# 01_Zasilacz.net
KiCad netlist of a schematic drawn in Altium Designer
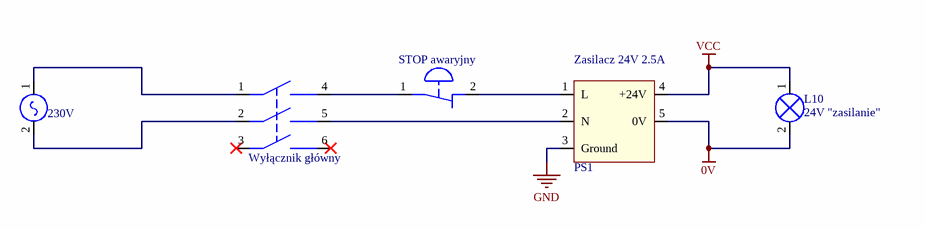
[diagram p0: [01] Zasilacz.SchDoc]

(export (version "E")
  (design (tool "Eeschema 10.0.6"))
  (components
    (comp (ref "*") (value "230V") (libsource (lib "Schlib2") (part "230V source")))
    (comp (ref "L10") (value "24V \"zasilanie\"") (libsource (lib "Schlib2") (part "Light")))
    (comp (ref "PS1") (value "Zasilacz 24V 2.5A") (libsource (lib "Schlib2") (part "Power supply")))
    (comp (ref "STOP awaryjny") (value "E-STOP 1 line") (libsource (lib "Schlib2") (part "E-STOP 1 line")))
    (comp (ref "Wyłącznik główny")
      (value "Power switch")
      (libsource (lib "Szczotkarka") (part "Power switch"))
    )
  )
  (nets
    (net (code "1") (name "0V") (class "Default")
      (node (ref "L10") (pin "2") (pinfunction "*_2") (pintype "passive"))
      (node (ref "PS1") (pin "5") (pinfunction "0V_5") (pintype "passive"))
    )
    (net (code "2") (name "GND") (class "Default")
      (node (ref "PS1") (pin "3") (pinfunction "Ground_3") (pintype "passive"))
    )
    (net (code "3") (name "Net-(PS1-L)") (class "Default")
      (node (ref "PS1") (pin "1") (pinfunction "L_1") (pintype "passive"))
      (node (ref "STOP awaryjny") (pin "2") (pinfunction "*_2") (pintype "passive"))
    )
    (net (code "4") (name "Net-(PS1-N)") (class "Default")
      (node (ref "PS1") (pin "2") (pinfunction "N_2") (pintype "passive"))
      (node (ref "Wyłącznik główny") (pin "5") (pinfunction "18_5") (pintype "passive"))
    )
    (net (code "5") (name "Net-(Wyłącznik główny-14)") (class "Default")
      (node (ref "*") (pin "1") (pinfunction "*_1") (pintype "passive"))
      (node (ref "Wyłącznik główny") (pin "1") (pinfunction "14_1") (pintype "passive"))
    )
    (net (code "6") (name "Net-(Wyłącznik główny-15)") (class "Default")
      (node (ref "*") (pin "2") (pinfunction "*_2") (pintype "passive"))
      (node (ref "Wyłącznik główny") (pin "2") (pinfunction "15_2") (pintype "passive"))
    )
    (net (code "7") (name "Net-(Wyłącznik główny-17)") (class "Default")
      (node (ref "STOP awaryjny") (pin "1") (pinfunction "*_1") (pintype "passive"))
      (node (ref "Wyłącznik główny") (pin "4") (pinfunction "17_4") (pintype "passive"))
    )
    (net (code "8") (name "VCC") (class "Default")
      (node (ref "L10") (pin "1") (pinfunction "*_1") (pintype "passive"))
      (node (ref "PS1") (pin "4") (pinfunction "+24V_4") (pintype "passive"))
    )
    (net (code "9") (name "unconnected-(Wyłącznik główny-16-Pad3)") (class "Default")
      (node (ref "Wyłącznik główny") (pin "3") (pinfunction "16_3") (pintype "passive+no_connect"))
    )
    (net (code "10") (name "unconnected-(Wyłącznik główny-19-Pad6)") (class "Default")
      (node (ref "Wyłącznik główny") (pin "6") (pinfunction "19_6") (pintype "passive+no_connect"))
    )
  )
)
